# MCU.net
KiCad netlist of a schematic drawn in Altium Designer
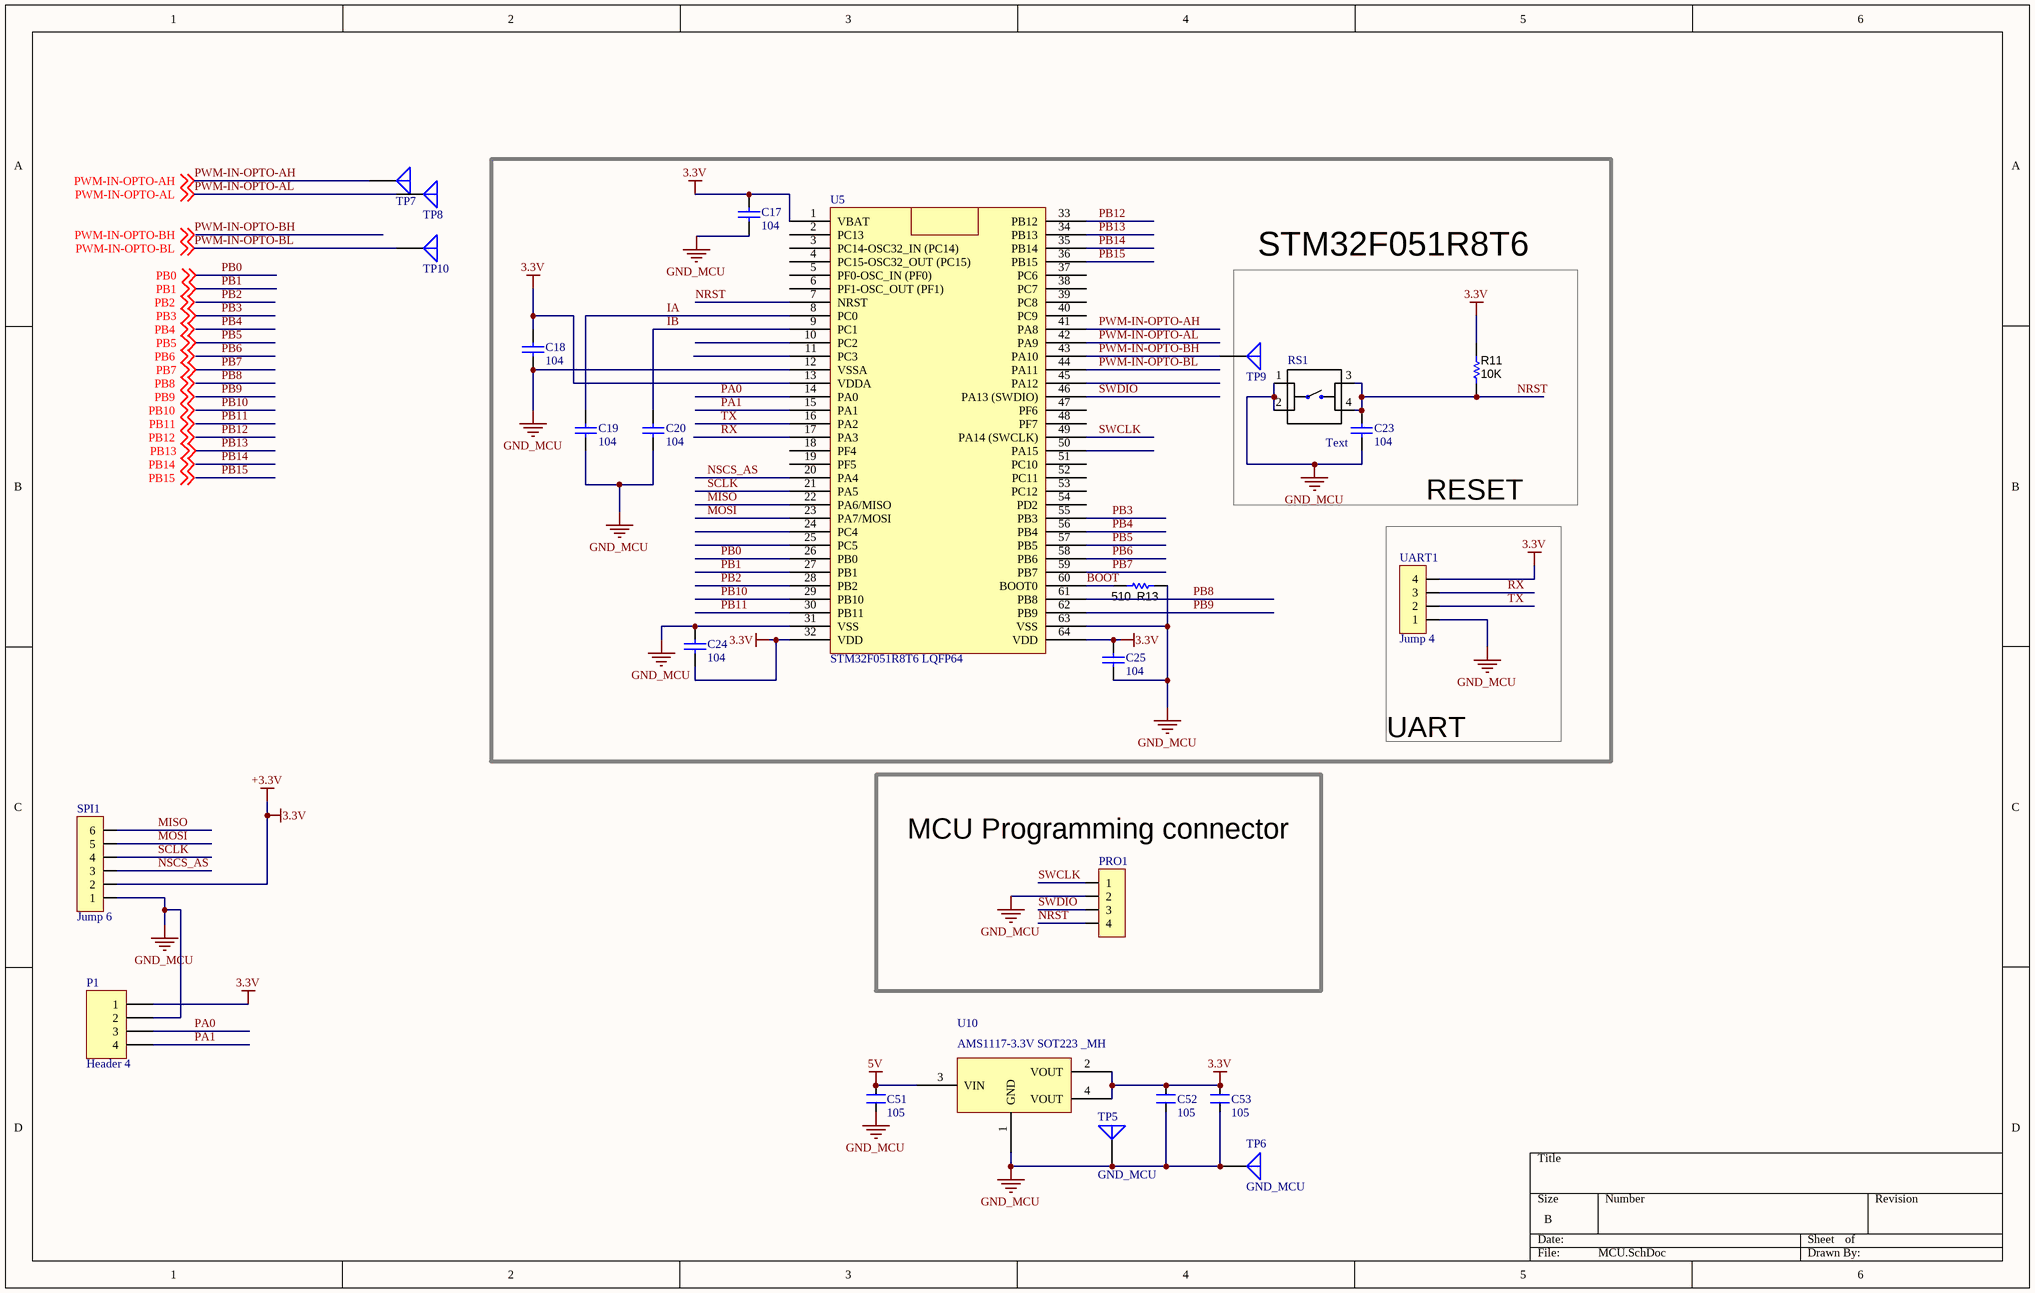
[diagram p0: MCU.SchDoc]

(export (version "E")
  (design (tool "Eeschema 10.0.6"))
  (components
    (comp (ref "C17")
      (value "104")
      (footprint "0603_Cap")
      (description "Ceramic Chip Capacitor - Standard")
      (fields (field (name "PUBLISHER") "Altium Limited"))
      (libsource (lib "mySch") (part "Capacitor 0805"))
    )
    (comp (ref "C18")
      (value "104")
      (footprint "0805_hv")
      (description "Ceramic Chip Capacitor - Standard")
      (fields (field (name "PUBLISHER") "Altium Limited"))
      (libsource (lib "mySch") (part "Capacitor 0805"))
    )
    (comp (ref "C19")
      (value "104")
      (footprint "TU_SMD_0805")
      (description "Ceramic Chip Capacitor - Standard")
      (fields (field (name "PUBLISHER") "Altium Limited"))
      (libsource (lib "mySch") (part "Capacitor 0805"))
    )
    (comp (ref "C20")
      (value "104")
      (footprint "TU_SMD_0805")
      (description "Ceramic Chip Capacitor - Standard")
      (fields (field (name "PUBLISHER") "Altium Limited"))
      (libsource (lib "mySch") (part "Capacitor 0805"))
    )
    (comp (ref "C23")
      (value "104")
      (footprint "0603_Cap")
      (description "Ceramic Chip Capacitor - Standard")
      (fields (field (name "PUBLISHER") "Altium Limited"))
      (libsource (lib "mySch") (part "Capacitor 0805"))
    )
    (comp (ref "C24")
      (value "104")
      (footprint "0805_hv")
      (description "Ceramic Chip Capacitor - Standard")
      (fields (field (name "PUBLISHER") "Altium Limited"))
      (libsource (lib "mySch") (part "Capacitor 0805"))
    )
    (comp (ref "C25")
      (value "104")
      (footprint "0805_hv")
      (description "Ceramic Chip Capacitor - Standard")
      (fields (field (name "PUBLISHER") "Altium Limited"))
      (libsource (lib "mySch") (part "Capacitor 0805"))
    )
    (comp (ref "C51")
      (value "105")
      (footprint "0805_HV")
      (description "Cap SMD")
      (libsource (lib "hatcatbietbay") (part "CM"))
    )
    (comp (ref "C52")
      (value "105")
      (footprint "0805_HV")
      (description "Cap SMD")
      (libsource (lib "hatcatbietbay") (part "CM"))
    )
    (comp (ref "C53")
      (value "105")
      (footprint "0805_HV")
      (description "Cap SMD")
      (libsource (lib "hatcatbietbay") (part "CM"))
    )
    (comp (ref "P1")
      (value "Header 4")
      (footprint "HDR1X4")
      (description "Header, 4-Pin")
      (fields (field (name "PUBLISHER") "Altium Limited"))
      (libsource (lib "Miscellaneous Connectors") (part "Header 4"))
    )
    (comp (ref "PRO1")
      (value "Jump 4_MH")
      (footprint "Jump 4")
      (description "Jump 4P 2.54")
      (libsource (lib "MH_DA_THU_VIEN_16122016") (part "Jump 4_MH"))
    )
    (comp (ref "R11")
      (value "10K")
      (footprint "0603_R")
      (description "RES, 100, 1%, 0.1 W, 0402")
      (fields
        (field (name "PARTNUMBER") "ERJ-2RKF1000X")
        (field (name "MANUFACTURER") "Panasonic")
        (field (name "PUBLISHER") "Texas Instruments")
      )
      (libsource (lib "mySch") (part "R nho"))
    )
    (comp (ref "R13")
      (value "510")
      (footprint "0603_R")
      (description "RES, 100, 1%, 0.1 W, 0402")
      (fields
        (field (name "PARTNUMBER") "ERJ-2RKF1000X")
        (field (name "MANUFACTURER") "Panasonic")
        (field (name "PUBLISHER") "Texas Instruments")
      )
      (libsource (lib "mySch") (part "R nho"))
    )
    (comp (ref "RS1")
      (value "*")
      (footprint "SMD Button 6X6")
      (description "FSM4JSMA=SMT,TACTILE,PB SWITCH")
      (fields (field (name "MP") "4-1437565-1") (field (name "MF") "TE Connectivity"))
      (libsource (lib "mySch") (part "SMD Button 6X6"))
    )
    (comp (ref "SPI1")
      (value "Jump 6")
      (footprint "ZH 1.5 6P")
      (description "Jump 6P 2.54")
      (libsource (lib "mySch") (part "Jump 6"))
    )
    (comp (ref "TP5")
      (value "GND_MCU")
      (footprint "PIN1")
      (description "Generic Antenna")
      (fields (field (name "PUBLISHER") "Altium Limited"))
      (libsource (lib "Miscellaneous Devices") (part "Antenna"))
    )
    (comp (ref "TP6")
      (value "GND_MCU")
      (footprint "PIN1")
      (description "Generic Antenna")
      (fields (field (name "PUBLISHER") "Altium Limited"))
      (libsource (lib "Miscellaneous Devices") (part "Antenna"))
    )
    (comp (ref "TP7")
      (value "PW1")
      (footprint "PIN1")
      (description "Generic Antenna")
      (fields (field (name "PUBLISHER") "Altium Limited"))
      (libsource (lib "Miscellaneous Devices") (part "Antenna"))
    )
    (comp (ref "TP8")
      (value "PW1")
      (footprint "PIN1")
      (description "Generic Antenna")
      (fields (field (name "PUBLISHER") "Altium Limited"))
      (libsource (lib "Miscellaneous Devices") (part "Antenna"))
    )
    (comp (ref "TP9")
      (value "PW")
      (footprint "PIN1")
      (description "Generic Antenna")
      (fields (field (name "PUBLISHER") "Altium Limited"))
      (libsource (lib "Miscellaneous Devices") (part "Antenna"))
    )
    (comp (ref "TP10")
      (value "PW1")
      (footprint "PIN1")
      (description "Generic Antenna")
      (fields (field (name "PUBLISHER") "Altium Limited"))
      (libsource (lib "Miscellaneous Devices") (part "Antenna"))
    )
    (comp (ref "U5")
      (value "STM32F051R8T6 LQFP64")
      (footprint "LQFP64")
      (description "STM32F051R8T6 LQFP64 _MH")
      (libsource (lib "mySch") (part "STM32F051R8T6 LQFP64 _MH"))
    )
    (comp (ref "U10")
      (value "AMS1117-3.3V SOT223 _MH")
      (footprint "SOT223")
      (libsource (lib "MH_DA_THU_VIEN_16122016") (part "AMS1117-3.3V SOT223 _MH"))
    )
    (comp (ref "UART1")
      (value "Jump 4")
      (footprint "HEADER 4")
      (description "Jump 4P 2.54")
      (libsource (lib "mySch") (part "Jump 4"))
    )
  )
  (nets
    (net (code "1") (name "+3.3V") (class "Default")
      (node (ref "C17") (pin "2") (pinfunction "2_2") (pintype "passive"))
      (node (ref "C18") (pin "2") (pinfunction "2_2") (pintype "passive"))
      (node (ref "C24") (pin "1") (pinfunction "1_1") (pintype "passive"))
      (node (ref "C25") (pin "2") (pinfunction "2_2") (pintype "passive"))
      (node (ref "C52") (pin "2") (pinfunction "2_2") (pintype "passive"))
      (node (ref "C53") (pin "2") (pinfunction "2_2") (pintype "passive"))
      (node (ref "P1") (pin "1") (pinfunction "1_1") (pintype "passive"))
      (node (ref "R11") (pin "2") (pinfunction "2_2") (pintype "passive"))
      (node (ref "SPI1") (pin "2") (pinfunction "2_2") (pintype "passive"))
      (node (ref "U10") (pin "2") (pinfunction "VOUT_2") (pintype "passive"))
      (node (ref "U10") (pin "4") (pinfunction "VOUT_4") (pintype "passive"))
      (node (ref "U5") (pin "1") (pinfunction "VBAT_1") (pintype "passive"))
      (node (ref "U5") (pin "13") (pinfunction "VDDA_13") (pintype "passive"))
      (node (ref "U5") (pin "32") (pinfunction "VDD_32") (pintype "passive"))
      (node (ref "U5") (pin "64") (pinfunction "VDD_64") (pintype "passive"))
      (node (ref "UART1") (pin "4") (pinfunction "4_4") (pintype "passive"))
    )
    (net (code "2") (name "/BOOT") (class "Default")
      (node (ref "R13") (pin "2") (pinfunction "2_2") (pintype "passive"))
      (node (ref "U5") (pin "60") (pinfunction "BOOT0_60") (pintype "passive"))
    )
    (net (code "3") (name "/IA") (class "Default")
      (node (ref "C19") (pin "2") (pinfunction "2_2") (pintype "passive"))
      (node (ref "U5") (pin "8") (pinfunction "PC0_8") (pintype "passive"))
    )
    (net (code "4") (name "/IB") (class "Default")
      (node (ref "C20") (pin "2") (pinfunction "2_2") (pintype "passive"))
      (node (ref "U5") (pin "9") (pinfunction "PC1_9") (pintype "passive"))
    )
    (net (code "5") (name "/MISO") (class "Default")
      (node (ref "SPI1") (pin "6") (pinfunction "6_6") (pintype "passive"))
      (node (ref "U5") (pin "22") (pinfunction "PA6/MISO_22") (pintype "passive"))
    )
    (net (code "6") (name "/MOSI") (class "Default")
      (node (ref "SPI1") (pin "5") (pinfunction "5_5") (pintype "passive"))
      (node (ref "U5") (pin "23") (pinfunction "PA7/MOSI_23") (pintype "passive"))
    )
    (net (code "7") (name "/NRST") (class "Default")
      (node (ref "C23") (pin "2") (pinfunction "2_2") (pintype "passive"))
      (node (ref "PRO1") (pin "4") (pinfunction "4_4") (pintype "passive"))
      (node (ref "R11") (pin "1") (pinfunction "1_1") (pintype "passive"))
      (node (ref "RS1") (pin "3") (pinfunction "3_3") (pintype "passive"))
      (node (ref "RS1") (pin "4") (pinfunction "4_4") (pintype "passive"))
      (node (ref "U5") (pin "7") (pinfunction "NRST_7") (pintype "passive"))
    )
    (net (code "8") (name "/NSCS_AS") (class "Default")
      (node (ref "SPI1") (pin "3") (pinfunction "3_3") (pintype "passive"))
      (node (ref "U5") (pin "20") (pinfunction "PA4_20") (pintype "passive"))
    )
    (net (code "9") (name "/PA0") (class "Default")
      (node (ref "P1") (pin "3") (pinfunction "3_3") (pintype "passive"))
      (node (ref "U5") (pin "14") (pinfunction "PA0_14") (pintype "passive"))
    )
    (net (code "10") (name "/PA1") (class "Default")
      (node (ref "P1") (pin "4") (pinfunction "4_4") (pintype "passive"))
      (node (ref "U5") (pin "15") (pinfunction "PA1_15") (pintype "passive"))
    )
    (net (code "11") (name "/RX") (class "Default")
      (node (ref "U5") (pin "17") (pinfunction "PA3_17") (pintype "passive"))
      (node (ref "UART1") (pin "3") (pinfunction "3_3") (pintype "passive"))
    )
    (net (code "12") (name "/SCLK") (class "Default")
      (node (ref "SPI1") (pin "4") (pinfunction "4_4") (pintype "passive"))
      (node (ref "U5") (pin "21") (pinfunction "PA5_21") (pintype "passive"))
    )
    (net (code "13") (name "/SWCLK") (class "Default")
      (node (ref "PRO1") (pin "1") (pinfunction "1_1") (pintype "passive"))
      (node (ref "U5") (pin "49") (pinfunction "PA14_(SWCLK)_49") (pintype "passive"))
    )
    (net (code "14") (name "/SWDIO") (class "Default")
      (node (ref "PRO1") (pin "3") (pinfunction "3_3") (pintype "passive"))
      (node (ref "U5") (pin "46") (pinfunction "PA13_(SWDIO)_46") (pintype "passive"))
    )
    (net (code "15") (name "/TX") (class "Default")
      (node (ref "U5") (pin "16") (pinfunction "PA2_16") (pintype "passive"))
      (node (ref "UART1") (pin "2") (pinfunction "2_2") (pintype "passive"))
    )
    (net (code "16") (name "5V") (class "Default")
      (node (ref "C51") (pin "2") (pinfunction "2_2") (pintype "passive"))
      (node (ref "U10") (pin "3") (pinfunction "VIN_3") (pintype "passive"))
    )
    (net (code "17") (name "GND_MCU") (class "Default")
      (node (ref "C17") (pin "1") (pinfunction "1_1") (pintype "passive"))
      (node (ref "C18") (pin "1") (pinfunction "1_1") (pintype "passive"))
      (node (ref "C19") (pin "1") (pinfunction "1_1") (pintype "passive"))
      (node (ref "C20") (pin "1") (pinfunction "1_1") (pintype "passive"))
      (node (ref "C23") (pin "1") (pinfunction "1_1") (pintype "passive"))
      (node (ref "C24") (pin "2") (pinfunction "2_2") (pintype "passive"))
      (node (ref "C25") (pin "1") (pinfunction "1_1") (pintype "passive"))
      (node (ref "C51") (pin "1") (pinfunction "1_1") (pintype "passive"))
      (node (ref "C52") (pin "1") (pinfunction "1_1") (pintype "passive"))
      (node (ref "C53") (pin "1") (pinfunction "1_1") (pintype "passive"))
      (node (ref "P1") (pin "2") (pinfunction "2_2") (pintype "passive"))
      (node (ref "PRO1") (pin "2") (pinfunction "2_2") (pintype "passive"))
      (node (ref "R13") (pin "1") (pinfunction "1_1") (pintype "passive"))
      (node (ref "RS1") (pin "1") (pinfunction "1_1") (pintype "passive"))
      (node (ref "RS1") (pin "2") (pinfunction "2_2") (pintype "passive"))
      (node (ref "SPI1") (pin "1") (pinfunction "1_1") (pintype "passive"))
      (node (ref "TP5") (pin "1") (pinfunction "A_1") (pintype "passive"))
      (node (ref "TP6") (pin "1") (pinfunction "A_1") (pintype "passive"))
      (node (ref "U10") (pin "1") (pinfunction "GND_1") (pintype "passive"))
      (node (ref "U5") (pin "12") (pinfunction "VSSA_12") (pintype "passive"))
      (node (ref "U5") (pin "31") (pinfunction "VSS_31") (pintype "passive"))
      (node (ref "U5") (pin "63") (pinfunction "VSS_63") (pintype "passive"))
      (node (ref "UART1") (pin "1") (pinfunction "1_1") (pintype "passive"))
    )
    (net (code "18") (name "PB0") (class "Default")
      (node (ref "U5") (pin "26") (pinfunction "PB0_26") (pintype "passive"))
    )
    (net (code "19") (name "PB1") (class "Default")
      (node (ref "U5") (pin "27") (pinfunction "PB1_27") (pintype "passive"))
    )
    (net (code "20") (name "PB2") (class "Default")
      (node (ref "U5") (pin "28") (pinfunction "PB2_28") (pintype "passive"))
    )
    (net (code "21") (name "PB3") (class "Default")
      (node (ref "U5") (pin "55") (pinfunction "PB3_55") (pintype "passive"))
    )
    (net (code "22") (name "PB4") (class "Default")
      (node (ref "U5") (pin "56") (pinfunction "PB4_56") (pintype "passive"))
    )
    (net (code "23") (name "PB5") (class "Default")
      (node (ref "U5") (pin "57") (pinfunction "PB5_57") (pintype "passive"))
    )
    (net (code "24") (name "PB6") (class "Default")
      (node (ref "U5") (pin "58") (pinfunction "PB6_58") (pintype "passive"))
    )
    (net (code "25") (name "PB7") (class "Default")
      (node (ref "U5") (pin "59") (pinfunction "PB7_59") (pintype "passive"))
    )
    (net (code "26") (name "PB8") (class "Default")
      (node (ref "U5") (pin "61") (pinfunction "PB8_61") (pintype "passive"))
    )
    (net (code "27") (name "PB9") (class "Default")
      (node (ref "U5") (pin "62") (pinfunction "PB9_62") (pintype "passive"))
    )
    (net (code "28") (name "PB10") (class "Default")
      (node (ref "U5") (pin "29") (pinfunction "PB10_29") (pintype "passive"))
    )
    (net (code "29") (name "PB11") (class "Default")
      (node (ref "U5") (pin "30") (pinfunction "PB11_30") (pintype "passive"))
    )
    (net (code "30") (name "PB12") (class "Default")
      (node (ref "U5") (pin "33") (pinfunction "PB12_33") (pintype "passive"))
    )
    (net (code "31") (name "PB13") (class "Default")
      (node (ref "U5") (pin "34") (pinfunction "PB13_34") (pintype "passive"))
    )
    (net (code "32") (name "PB14") (class "Default")
      (node (ref "U5") (pin "35") (pinfunction "PB14_35") (pintype "passive"))
    )
    (net (code "33") (name "PB15") (class "Default")
      (node (ref "U5") (pin "36") (pinfunction "PB15_36") (pintype "passive"))
    )
    (net (code "34") (name "PWM-IN-OPTO-AH") (class "Default")
      (node (ref "TP7") (pin "1") (pinfunction "A_1") (pintype "passive"))
      (node (ref "U5") (pin "41") (pinfunction "PA8_41") (pintype "passive"))
    )
    (net (code "35") (name "PWM-IN-OPTO-AL") (class "Default")
      (node (ref "TP8") (pin "1") (pinfunction "A_1") (pintype "passive"))
      (node (ref "U5") (pin "42") (pinfunction "PA9_42") (pintype "passive"))
    )
    (net (code "36") (name "PWM-IN-OPTO-BH") (class "Default")
      (node (ref "TP9") (pin "1") (pinfunction "A_1") (pintype "passive"))
      (node (ref "U5") (pin "43") (pinfunction "PA10_43") (pintype "passive"))
    )
    (net (code "37") (name "PWM-IN-OPTO-BL") (class "Default")
      (node (ref "TP10") (pin "1") (pinfunction "A_1") (pintype "passive"))
      (node (ref "U5") (pin "44") (pinfunction "PA11_44") (pintype "passive"))
    )
    (net (code "38") (name "unconnected-(U5-PA12-Pad45)") (class "Default")
      (node (ref "U5") (pin "45") (pinfunction "PA12_45") (pintype "passive"))
    )
    (net (code "39") (name "unconnected-(U5-PA15-Pad50)") (class "Default")
      (node (ref "U5") (pin "50") (pinfunction "PA15_50") (pintype "passive"))
    )
    (net (code "40") (name "unconnected-(U5-PC2-Pad10)") (class "Default")
      (node (ref "U5") (pin "10") (pinfunction "PC2_10") (pintype "passive"))
    )
    (net (code "41") (name "unconnected-(U5-PC3-Pad11)") (class "Default")
      (node (ref "U5") (pin "11") (pinfunction "PC3_11") (pintype "passive"))
    )
    (net (code "42") (name "unconnected-(U5-PC4-Pad24)") (class "Default")
      (node (ref "U5") (pin "24") (pinfunction "PC4_24") (pintype "passive"))
    )
    (net (code "43") (name "unconnected-(U5-PC5-Pad25)") (class "Default")
      (node (ref "U5") (pin "25") (pinfunction "PC5_25") (pintype "passive"))
    )
    (net (code "44") (name "unconnected-(U5-PC6-Pad37)") (class "Default")
      (node (ref "U5") (pin "37") (pinfunction "PC6_37") (pintype "passive"))
    )
    (net (code "45") (name "unconnected-(U5-PC7-Pad38)") (class "Default")
      (node (ref "U5") (pin "38") (pinfunction "PC7_38") (pintype "passive"))
    )
    (net (code "46") (name "unconnected-(U5-PC8-Pad39)") (class "Default")
      (node (ref "U5") (pin "39") (pinfunction "PC8_39") (pintype "passive"))
    )
    (net (code "47") (name "unconnected-(U5-PC9-Pad40)") (class "Default")
      (node (ref "U5") (pin "40") (pinfunction "PC9_40") (pintype "passive"))
    )
    (net (code "48") (name "unconnected-(U5-PC10-Pad51)") (class "Default")
      (node (ref "U5") (pin "51") (pinfunction "PC10_51") (pintype "passive"))
    )
    (net (code "49") (name "unconnected-(U5-PC11-Pad52)") (class "Default")
      (node (ref "U5") (pin "52") (pinfunction "PC11_52") (pintype "passive"))
    )
    (net (code "50") (name "unconnected-(U5-PC12-Pad53)") (class "Default")
      (node (ref "U5") (pin "53") (pinfunction "PC12_53") (pintype "passive"))
    )
    (net (code "51") (name "unconnected-(U5-PC13-Pad2)") (class "Default")
      (node (ref "U5") (pin "2") (pinfunction "PC13_2") (pintype "passive"))
    )
    (net (code "52") (name "unconnected-(U5-PC14-OSC32_IN_(PC14)-Pad3)") (class "Default")
      (node (ref "U5") (pin "3") (pinfunction "PC14-OSC32_IN_(PC14)_3") (pintype "passive"))
    )
    (net (code "53") (name "unconnected-(U5-PC15-OSC32_OUT_(PC15)-Pad4)") (class "Default")
      (node (ref "U5") (pin "4") (pinfunction "PC15-OSC32_OUT_(PC15)_4") (pintype "passive"))
    )
    (net (code "54") (name "unconnected-(U5-PD2-Pad54)") (class "Default")
      (node (ref "U5") (pin "54") (pinfunction "PD2_54") (pintype "passive"))
    )
    (net (code "55") (name "unconnected-(U5-PF0-OSC_IN_(PF0)-Pad5)") (class "Default")
      (node (ref "U5") (pin "5") (pinfunction "PF0-OSC_IN_(PF0)_5") (pintype "passive"))
    )
    (net (code "56") (name "unconnected-(U5-PF1-OSC_OUT_(PF1)-Pad6)") (class "Default")
      (node (ref "U5") (pin "6") (pinfunction "PF1-OSC_OUT_(PF1)_6") (pintype "passive"))
    )
    (net (code "57") (name "unconnected-(U5-PF4-Pad18)") (class "Default")
      (node (ref "U5") (pin "18") (pinfunction "PF4_18") (pintype "passive"))
    )
    (net (code "58") (name "unconnected-(U5-PF5-Pad19)") (class "Default")
      (node (ref "U5") (pin "19") (pinfunction "PF5_19") (pintype "passive"))
    )
    (net (code "59") (name "unconnected-(U5-PF6-Pad47)") (class "Default")
      (node (ref "U5") (pin "47") (pinfunction "PF6_47") (pintype "passive"))
    )
    (net (code "60") (name "unconnected-(U5-PF7-Pad48)") (class "Default")
      (node (ref "U5") (pin "48") (pinfunction "PF7_48") (pintype "passive"))
    )
  )
)
